# Main.net
KiCad netlist of a schematic drawn in Altium Designer
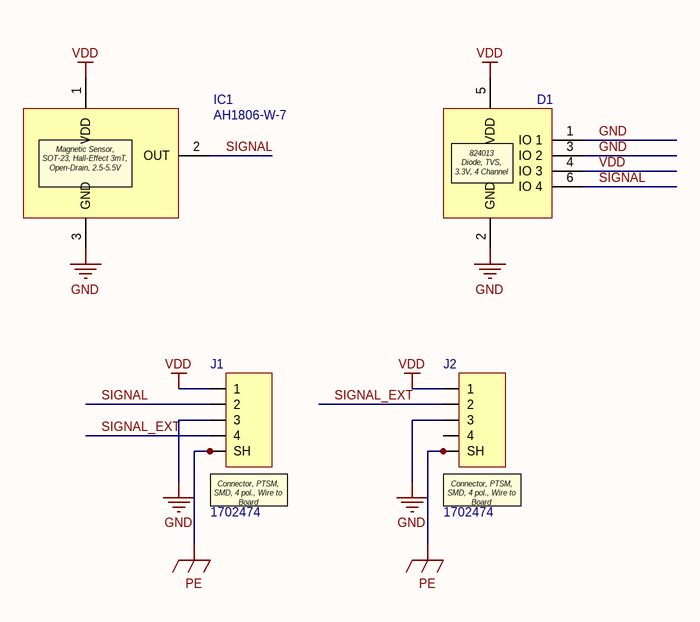
[diagram p0: Main.SchDoc]

(export (version "E")
  (design (tool "Eeschema 10.0.6"))
  (components
    (comp (ref "D1")
      (value "824013")
      (footprint "SOT-23-6")
      (description "Diode, TVS, 3.3V, 4 Channel")
      (fields (field (name "MANUFACTURER") "Würth Electronics"))
      (libsource (lib "Createc Circuitstudio Library") (part "824013"))
    )
    (comp (ref "IC1")
      (value "AH1806-W-7")
      (footprint "SOT-23")
      (description "Magnetic Sensor, SOT-23, Hall-Effect 3mT, Open-Drain, 2.5-5.5V")
      (fields (field (name "MANUFACTURER") "Diodes Inc.") (field (name "MPN") "AH1806-W-7"))
      (libsource (lib "Schlib1") (part "AH1806-W-7"))
    )
    (comp (ref "J1")
      (value "1702474")
      (footprint "1702474")
      (description "Connector, PTSM, SMD, 4 pol., Wire to Board")
      (fields (field (name "MANUFACTURER") "Phoenix Contact") (field (name "MPN") "1702474"))
      (libsource (lib "Schlib1") (part "1702474"))
    )
    (comp (ref "J2")
      (value "1702474")
      (footprint "1702474")
      (description "Connector, PTSM, SMD, 4 pol., Wire to Board")
      (fields (field (name "MANUFACTURER") "Phoenix Contact") (field (name "MPN") "1702474"))
      (libsource (lib "Schlib1") (part "1702474"))
    )
  )
  (nets
    (net (code "1") (name "/SIGNAL") (class "Default")
      (node (ref "D1") (pin "6") (pinfunction "IO_4_6") (pintype "passive"))
      (node (ref "IC1") (pin "2") (pinfunction "OUT_2") (pintype "passive"))
      (node (ref "J1") (pin "2") (pinfunction "2_2") (pintype "passive"))
    )
    (net (code "2") (name "/SIGNAL_EXT") (class "Default")
      (node (ref "J1") (pin "4") (pinfunction "4_4") (pintype "passive"))
      (node (ref "J2") (pin "2") (pinfunction "2_2") (pintype "passive"))
    )
    (net (code "3") (name "GND") (class "Default")
      (node (ref "D1") (pin "1") (pinfunction "IO_1_1") (pintype "passive"))
      (node (ref "D1") (pin "2") (pinfunction "GND_2") (pintype "passive"))
      (node (ref "D1") (pin "3") (pinfunction "IO_2_3") (pintype "passive"))
      (node (ref "IC1") (pin "3") (pinfunction "GND_3") (pintype "passive"))
      (node (ref "J1") (pin "3") (pinfunction "3_3") (pintype "passive"))
      (node (ref "J2") (pin "3") (pinfunction "3_3") (pintype "passive"))
    )
    (net (code "4") (name "PE") (class "Default")
      (node (ref "J1") (pin "SH1") (pinfunction "SH_SH1") (pintype "passive"))
      (node (ref "J1") (pin "SH2") (pinfunction "SH2_SH2") (pintype "passive"))
      (node (ref "J2") (pin "SH1") (pinfunction "SH_SH1") (pintype "passive"))
      (node (ref "J2") (pin "SH2") (pinfunction "SH2_SH2") (pintype "passive"))
    )
    (net (code "5") (name "VDD") (class "Default")
      (node (ref "D1") (pin "4") (pinfunction "IO_3_4") (pintype "passive"))
      (node (ref "D1") (pin "5") (pinfunction "VDD_5") (pintype "passive"))
      (node (ref "IC1") (pin "1") (pinfunction "VDD_1") (pintype "passive"))
      (node (ref "J1") (pin "1") (pinfunction "1_1") (pintype "passive"))
      (node (ref "J2") (pin "1") (pinfunction "1_1") (pintype "passive"))
    )
    (net (code "6") (name "unconnected-(J2-Pad4)") (class "Default")
      (node (ref "J2") (pin "4") (pinfunction "4_4") (pintype "passive"))
    )
  )
)
